# Management_of_Charging_Discharging_Tri-a.net
KiCad netlist of a schematic drawn in Altium Designer
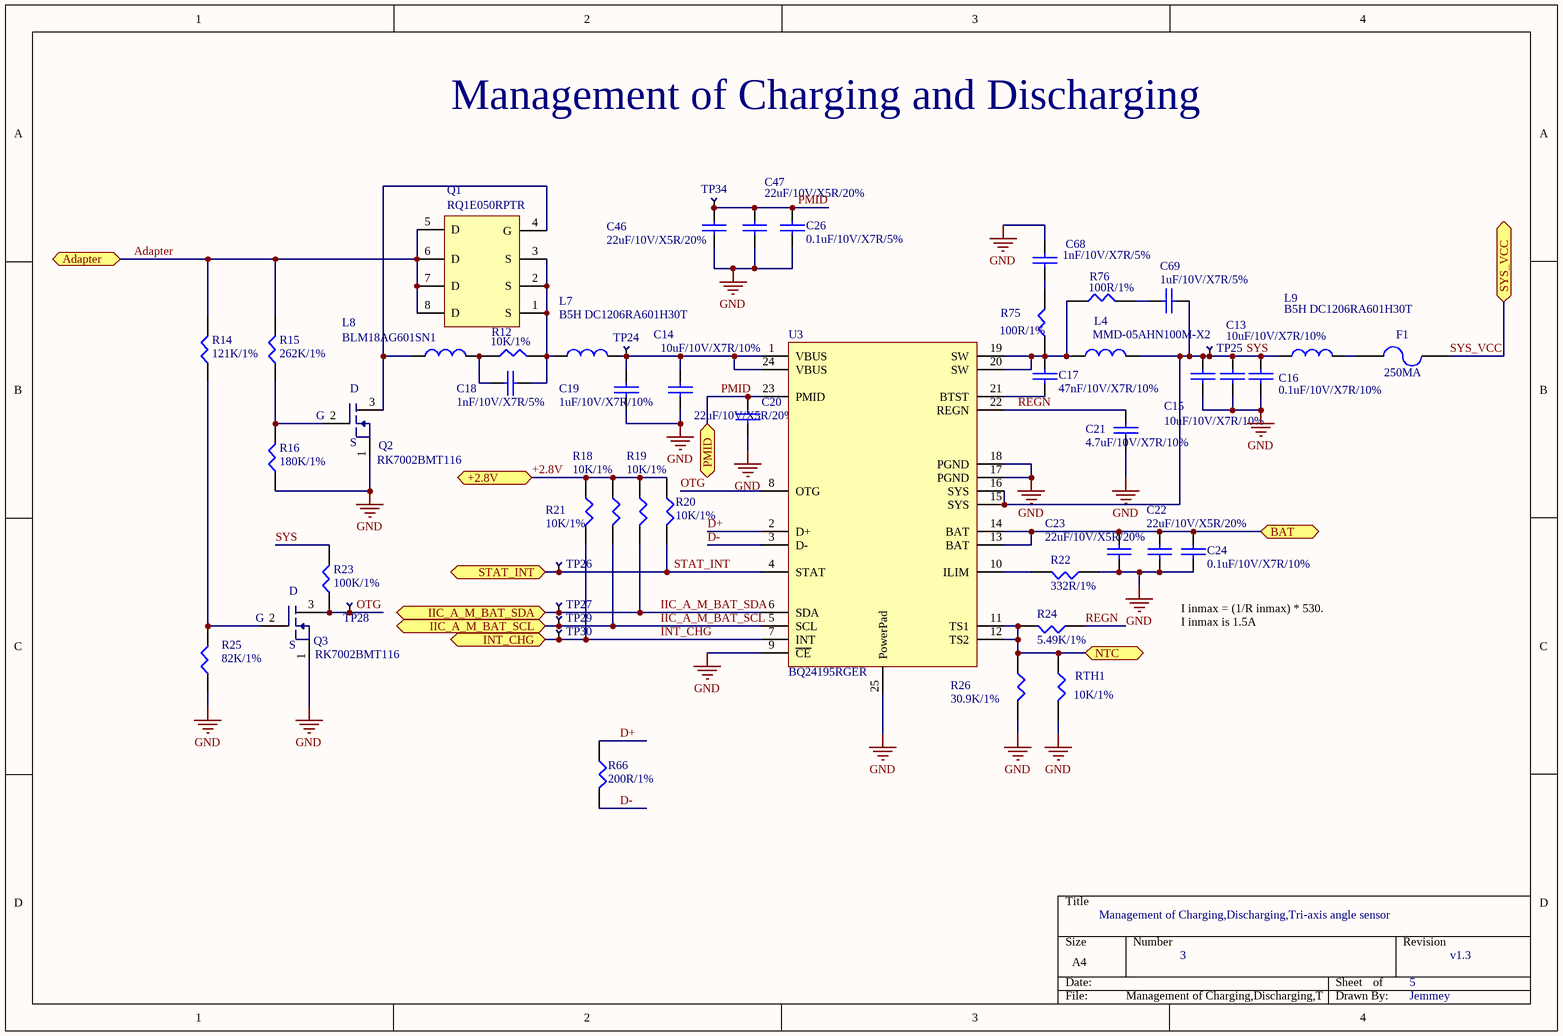
[diagram p0: Management of Charging,Discharging,Tri-axis angle sensor.SchDoc]

(export (version "E")
  (design (tool "Eeschema 10.0.6"))
  (components
    (comp (ref "C13")
      (value "10uF/10V/X7R/10%")
      (footprint "0603C")
      (description "厂家：Murata，型号：GRM188R61A106KE69D")
      (libsource (lib "*") (part "CAP"))
    )
    (comp (ref "C14")
      (value "10uF/10V/X7R/10%")
      (footprint "0603C")
      (description "厂家：Murata，型号：GRM188R61A106KE69D")
      (libsource (lib "*") (part "CAP"))
    )
    (comp (ref "C15")
      (value "10uF/10V/X7R/10%")
      (footprint "0603C")
      (description "厂家：Murata，型号：GRM188R61A106KE69D")
      (libsource (lib "*") (part "CAP"))
    )
    (comp (ref "C16")
      (value "0.1uF/10V/X7R/10%")
      (footprint "0402C")
      (description "厂家：Murata，型号：GRM155R71A104KA01D")
      (libsource (lib "*") (part "CAP"))
    )
    (comp (ref "C17")
      (value "47nF/10V/X7R/10%")
      (footprint "0402C")
      (description "厂家：Murata，型号：GRM155R71H473KE14D")
      (libsource (lib "*") (part "CAP"))
    )
    (comp (ref "C18")
      (value "1nF/10V/X7R/5%")
      (footprint "0402C")
      (description "厂家：Murata，型号：GRM1555C1H102JA01D")
      (libsource (lib "*") (part "CAP"))
    )
    (comp (ref "C19")
      (value "1uF/10V/X7R/10%")
      (footprint "0402C")
      (description "厂家：Murata，型号：GRM155R61C105KA12D")
      (libsource (lib "*") (part "CAP"))
    )
    (comp (ref "C20")
      (value "22uF/10V/X5R/20%")
      (footprint "0603C")
      (description "厂家：Murata，型号：GRM188R61A226ME15D")
      (libsource (lib "*") (part "CAP"))
    )
    (comp (ref "C21")
      (value "4.7uF/10V/X7R/10%")
      (footprint "0603C")
      (description "厂家：Murata，型号：GRM188R61A475KE15D")
      (libsource (lib "*") (part "CAP"))
    )
    (comp (ref "C22")
      (value "22uF/10V/X5R/20%")
      (footprint "0603C")
      (description "厂家：Murata，型号：GRM188R61A226ME15D")
      (libsource (lib "*") (part "CAP"))
    )
    (comp (ref "C23")
      (value "22uF/10V/X5R/20%")
      (footprint "0603C")
      (description "厂家：Murata，型号：GRM188R61A226ME15D")
      (libsource (lib "*") (part "CAP"))
    )
    (comp (ref "C24")
      (value "0.1uF/10V/X7R/10%")
      (footprint "0402C")
      (description "厂家：Murata，型号：GRM155R71A104KA01D")
      (libsource (lib "*") (part "CAP"))
    )
    (comp (ref "C26")
      (value "0.1uF/10V/X7R/5%")
      (footprint "0402C")
      (description "厂家：Murata，型号：GRM1555C1H102JA01D")
      (libsource (lib "*") (part "CAP"))
    )
    (comp (ref "C46")
      (value "22uF/10V/X5R/20%")
      (footprint "0603C")
      (description "厂家：Murata，型号：GRM188R61A226ME15D")
      (libsource (lib "*") (part "CAP"))
    )
    (comp (ref "C47")
      (value "22uF/10V/X5R/20%")
      (footprint "0603C")
      (description "厂家：Murata，型号：GRM188R61A226ME15D")
      (libsource (lib "*") (part "CAP"))
    )
    (comp (ref "C68")
      (value "1nF/10V/X7R/5%")
      (footprint "0603C")
      (description "厂家：Murata，型号：")
      (libsource (lib "*") (part "CAP"))
    )
    (comp (ref "C69")
      (value "1uF/10V/X7R/5%")
      (footprint "0603C")
      (description "厂家：Murata，型号：GRM1555C1H102JA01D")
      (libsource (lib "*") (part "CAP"))
    )
    (comp (ref "F1")
      (value "250MA")
      (footprint "1206-FUSE")
      (description "厂家：万瑞和，型号：WH1206-050")
      (libsource (lib "*") (part "FUSE2"))
    )
    (comp (ref "L4")
      (value "MMD-05AHN100M-X2")
      (footprint "MMD")
      (description "厂家：Mag，型号：MMD-05AHN100M-X2")
      (libsource (lib "Amber") (part "CHOKE"))
    )
    (comp (ref "L7")
      (value "B5H DC1206RA601H30T")
      (footprint "1206")
      (description "厂家：宇磁，型号：B5H DC1206RA601H30T")
      (libsource (lib "Amber") (part "CHOKE"))
    )
    (comp (ref "L8")
      (value "BLM18AG601SN1")
      (footprint "0603R")
      (description "厂家：MURATA，型号：BLM18AG601SN1")
      (libsource (lib "Amber") (part "CHOKE"))
    )
    (comp (ref "L9")
      (value "B5H DC1206RA601H30T")
      (footprint "1206")
      (description "厂家：宇磁，型号：B5H DC1206RA601H30T")
      (libsource (lib "Amber") (part "CHOKE"))
    )
    (comp (ref "Q1")
      (value "RQ1E050RPTR")
      (footprint "TSMT8")
      (description "厂家：ROHM，型号：   RQ1E050RPTR")
      (libsource (lib "Amber") (part "RQ1E050RP"))
    )
    (comp (ref "Q2")
      (value "RK7002BMT116")
      (footprint "SOT23")
      (description "厂家：Vishay，型号：RK7002BMT116")
      (libsource (lib "Amber") (part "RK7002BMT116"))
    )
    (comp (ref "Q3")
      (value "RK7002BMT116")
      (footprint "SOT23")
      (description "厂家：Vishay，型号：RK7002BMT116")
      (libsource (lib "Amber") (part "RK7002BMT116"))
    )
    (comp (ref "R12")
      (value "10K/1%")
      (footprint "0402R")
      (description "厂家：Yageo，型号：RC0402FR-0710KL")
      (libsource (lib "*") (part "RES1"))
    )
    (comp (ref "R14")
      (value "121K/1%")
      (footprint "0402R")
      (description "厂家：Yageo，型号：RC0402FR-07121KL")
      (libsource (lib "*") (part "RES1"))
    )
    (comp (ref "R15")
      (value "262K/1%")
      (footprint "0402R")
      (description "厂家：Yageo，型号：RC0402FR-07262KL")
      (libsource (lib "*") (part "RES1"))
    )
    (comp (ref "R16")
      (value "180K/1%")
      (footprint "0402R")
      (description "厂家：Yageo，型号：RC0402FR-07180KL")
      (libsource (lib "*") (part "RES1"))
    )
    (comp (ref "R18")
      (value "10K/1%")
      (footprint "0402R")
      (description "厂家：Yageo，型号：RC0402FR-0710KL")
      (libsource (lib "*") (part "RES1"))
    )
    (comp (ref "R19")
      (value "10K/1%")
      (footprint "0402R")
      (description "厂家：Yageo，型号：RC0402FR-0710KL")
      (libsource (lib "*") (part "RES1"))
    )
    (comp (ref "R20")
      (value "10K/1%")
      (footprint "0402R")
      (description "厂家：Yageo，型号：RC0402FR-0710KL")
      (libsource (lib "*") (part "RES1"))
    )
    (comp (ref "R21")
      (value "10K/1%")
      (footprint "0402R")
      (description "厂家：Yageo，型号：RC0402FR-0710KL")
      (libsource (lib "*") (part "RES1"))
    )
    (comp (ref "R22")
      (value "332R/1%")
      (footprint "0402R")
      (description "厂家：Yageo，型号：RC0402FR-07332RL")
      (libsource (lib "*") (part "RES1"))
    )
    (comp (ref "R23")
      (value "100K/1%")
      (footprint "0402R")
      (description "厂家：Yageo，型号：RC0402FR-07100KL")
      (libsource (lib "*") (part "RES1"))
    )
    (comp (ref "R24")
      (value "5.49K/1%")
      (footprint "0402R")
      (description "厂家：Yageo，型号：RC0402FR-075K49L")
      (libsource (lib "*") (part "RES1"))
    )
    (comp (ref "R25")
      (value "82K/1%")
      (footprint "0402R")
      (description "厂家：Yageo，型号：RC0402FR-0782KL")
      (libsource (lib "*") (part "RES1"))
    )
    (comp (ref "R26")
      (value "30.9K/1%")
      (footprint "0402R")
      (description "厂家：Yageo，型号：RC0402FR-0730K9L")
      (libsource (lib "*") (part "RES1"))
    )
    (comp (ref "R66")
      (value "200R/1%")
      (footprint "0402R")
      (description "厂家：Yageo，型号：RC0402FR-07200RL")
      (libsource (lib "*") (part "RES1"))
    )
    (comp (ref "R75")
      (value "100R/1%")
      (footprint "0603R")
      (description "厂家：Yageo，型号：RC0402FR-0710KL")
      (libsource (lib "*") (part "RES1"))
    )
    (comp (ref "R76")
      (value "100R/1%")
      (footprint "0603R")
      (description "厂家：Yageo，型号：RC0402FR-0710KL")
      (libsource (lib "*") (part "RES1"))
    )
    (comp (ref "RTH1")
      (value "10K/1%")
      (footprint "0402R")
      (description "厂家：Yageo，型号：RC0402FR-0710KL")
      (libsource (lib "*") (part "RES1"))
    )
    (comp (ref "TP24")
      (value "TEST")
      (footprint "Test Pad")
      (description "Test Point")
      (libsource (lib "Amber") (part "TEST"))
    )
    (comp (ref "TP25")
      (value "TEST")
      (footprint "Test Pad")
      (description "Test Point")
      (libsource (lib "Amber") (part "TEST"))
    )
    (comp (ref "TP26")
      (value "TEST")
      (footprint "Test Pad")
      (description "Test Point")
      (libsource (lib "Amber") (part "TEST"))
    )
    (comp (ref "TP27")
      (value "TEST")
      (footprint "Test Pad")
      (description "Test Point")
      (libsource (lib "Amber") (part "TEST"))
    )
    (comp (ref "TP28")
      (value "TEST")
      (footprint "Test Pad")
      (description "Test Point")
      (libsource (lib "Amber") (part "TEST"))
    )
    (comp (ref "TP29")
      (value "TEST")
      (footprint "Test Pad")
      (description "Test Point")
      (libsource (lib "Amber") (part "TEST"))
    )
    (comp (ref "TP30")
      (value "TEST")
      (footprint "Test Pad")
      (description "Test Point")
      (libsource (lib "Amber") (part "TEST"))
    )
    (comp (ref "TP34")
      (value "TEST")
      (footprint "Test Pad")
      (description "Test Point")
      (libsource (lib "Amber") (part "TEST"))
    )
    (comp (ref "U3")
      (value "BQ24195RGER")
      (footprint "RGE")
      (description "厂家：TI，型号：BQ24195RGER")
      (libsource (lib "Amber") (part "BQ24195L"))
    )
  )
  (nets
    (net (code "1") (name "/+2.8V") (class "Default")
      (node (ref "R18") (pin "1") (pinfunction "1_1") (pintype "passive"))
      (node (ref "R19") (pin "1") (pinfunction "1_1") (pintype "passive"))
      (node (ref "R20") (pin "1") (pinfunction "1_1") (pintype "passive"))
      (node (ref "R21") (pin "1") (pinfunction "1_1") (pintype "passive"))
    )
    (net (code "2") (name "/Adapter") (class "Default")
      (node (ref "Q1") (pin "5") (pinfunction "D_5") (pintype "passive"))
      (node (ref "Q1") (pin "6") (pinfunction "D_6") (pintype "passive"))
      (node (ref "Q1") (pin "7") (pinfunction "D_7") (pintype "passive"))
      (node (ref "Q1") (pin "8") (pinfunction "D_8") (pintype "passive"))
      (node (ref "R14") (pin "2") (pinfunction "2_2") (pintype "passive"))
      (node (ref "R15") (pin "2") (pinfunction "2_2") (pintype "passive"))
    )
    (net (code "3") (name "/BAT") (class "Default")
      (node (ref "C22") (pin "1") (pinfunction "1_1") (pintype "passive"))
      (node (ref "C23") (pin "1") (pinfunction "1_1") (pintype "passive"))
      (node (ref "C24") (pin "1") (pinfunction "1_1") (pintype "passive"))
      (node (ref "U3") (pin "13") (pinfunction "BAT_13") (pintype "passive"))
      (node (ref "U3") (pin "14") (pinfunction "BAT_14") (pintype "passive"))
    )
    (net (code "4") (name "/D+") (class "Default")
      (node (ref "R66") (pin "1") (pinfunction "1_1") (pintype "passive"))
      (node (ref "U3") (pin "2") (pinfunction "D+_2") (pintype "passive"))
    )
    (net (code "5") (name "/D-") (class "Default")
      (node (ref "R66") (pin "2") (pinfunction "2_2") (pintype "passive"))
      (node (ref "U3") (pin "3") (pinfunction "D-_3") (pintype "passive"))
    )
    (net (code "6") (name "/IIC_A_M_BAT_SCL") (class "Default")
      (node (ref "R18") (pin "2") (pinfunction "2_2") (pintype "passive"))
      (node (ref "TP29") (pin "1") (pinfunction "1_1") (pintype "passive"))
      (node (ref "U3") (pin "5") (pinfunction "SCL_5") (pintype "passive"))
    )
    (net (code "7") (name "/IIC_A_M_BAT_SDA") (class "Default")
      (node (ref "R19") (pin "2") (pinfunction "2_2") (pintype "passive"))
      (node (ref "TP27") (pin "1") (pinfunction "1_1") (pintype "passive"))
      (node (ref "U3") (pin "6") (pinfunction "SDA_6") (pintype "passive"))
    )
    (net (code "8") (name "/INT_CHG") (class "Default")
      (node (ref "R21") (pin "2") (pinfunction "2_2") (pintype "passive"))
      (node (ref "TP30") (pin "1") (pinfunction "1_1") (pintype "passive"))
      (node (ref "U3") (pin "7") (pinfunction "INT_7") (pintype "passive"))
    )
    (net (code "9") (name "/NTC") (class "Default")
      (node (ref "R24") (pin "2") (pinfunction "2_2") (pintype "passive"))
      (node (ref "R26") (pin "1") (pinfunction "1_1") (pintype "passive"))
      (node (ref "RTH1") (pin "1") (pinfunction "1_1") (pintype "passive"))
      (node (ref "U3") (pin "11") (pinfunction "TS1_11") (pintype "passive"))
      (node (ref "U3") (pin "12") (pinfunction "TS2_12") (pintype "passive"))
    )
    (net (code "10") (name "/OTG") (class "Default")
      (node (ref "Q3") (pin "3") (pinfunction "D_3") (pintype "passive"))
      (node (ref "R23") (pin "1") (pinfunction "1_1") (pintype "passive"))
      (node (ref "TP28") (pin "1") (pinfunction "1_1") (pintype "passive"))
      (node (ref "U3") (pin "8") (pinfunction "OTG_8") (pintype "passive"))
    )
    (net (code "11") (name "/PMID") (class "Default")
      (node (ref "C20") (pin "1") (pinfunction "1_1") (pintype "passive"))
      (node (ref "C26") (pin "2") (pinfunction "2_2") (pintype "passive"))
      (node (ref "C46") (pin "1") (pinfunction "1_1") (pintype "passive"))
      (node (ref "C47") (pin "1") (pinfunction "1_1") (pintype "passive"))
      (node (ref "TP34") (pin "1") (pinfunction "1_1") (pintype "passive"))
      (node (ref "U3") (pin "23") (pinfunction "PMID_23") (pintype "passive"))
    )
    (net (code "12") (name "/REGN") (class "Default")
      (node (ref "C21") (pin "1") (pinfunction "1_1") (pintype "passive"))
      (node (ref "R24") (pin "1") (pinfunction "1_1") (pintype "passive"))
      (node (ref "U3") (pin "22") (pinfunction "REGN_22") (pintype "passive"))
    )
    (net (code "13") (name "/STAT_INT") (class "Default")
      (node (ref "R20") (pin "2") (pinfunction "2_2") (pintype "passive"))
      (node (ref "TP26") (pin "1") (pinfunction "1_1") (pintype "passive"))
      (node (ref "U3") (pin "4") (pinfunction "STAT_4") (pintype "passive"))
    )
    (net (code "14") (name "/SYS") (class "Default")
      (node (ref "C13") (pin "1") (pinfunction "1_1") (pintype "passive"))
      (node (ref "C15") (pin "1") (pinfunction "1_1") (pintype "passive"))
      (node (ref "C16") (pin "1") (pinfunction "1_1") (pintype "passive"))
      (node (ref "C69") (pin "1") (pinfunction "1_1") (pintype "passive"))
      (node (ref "L4") (pin "2") (pinfunction "2_2") (pintype "passive"))
      (node (ref "L9") (pin "1") (pinfunction "1_1") (pintype "passive"))
      (node (ref "R23") (pin "2") (pinfunction "2_2") (pintype "passive"))
      (node (ref "TP25") (pin "1") (pinfunction "1_1") (pintype "passive"))
      (node (ref "U3") (pin "15") (pinfunction "SYS_15") (pintype "passive"))
      (node (ref "U3") (pin "16") (pinfunction "SYS_16") (pintype "passive"))
    )
    (net (code "15") (name "/SYS_VCC") (class "Default")
      (node (ref "F1") (pin "1") (pinfunction "1_1") (pintype "passive"))
    )
    (net (code "16") (name "GND") (class "Default")
      (node (ref "C13") (pin "2") (pinfunction "2_2") (pintype "passive"))
      (node (ref "C14") (pin "2") (pinfunction "2_2") (pintype "passive"))
      (node (ref "C15") (pin "2") (pinfunction "2_2") (pintype "passive"))
      (node (ref "C16") (pin "2") (pinfunction "2_2") (pintype "passive"))
      (node (ref "C19") (pin "2") (pinfunction "2_2") (pintype "passive"))
      (node (ref "C20") (pin "2") (pinfunction "2_2") (pintype "passive"))
      (node (ref "C21") (pin "2") (pinfunction "2_2") (pintype "passive"))
      (node (ref "C22") (pin "2") (pinfunction "2_2") (pintype "passive"))
      (node (ref "C23") (pin "2") (pinfunction "2_2") (pintype "passive"))
      (node (ref "C24") (pin "2") (pinfunction "2_2") (pintype "passive"))
      (node (ref "C26") (pin "1") (pinfunction "1_1") (pintype "passive"))
      (node (ref "C46") (pin "2") (pinfunction "2_2") (pintype "passive"))
      (node (ref "C47") (pin "2") (pinfunction "2_2") (pintype "passive"))
      (node (ref "C68") (pin "2") (pinfunction "2_2") (pintype "passive"))
      (node (ref "Q2") (pin "1") (pinfunction "S_1") (pintype "passive"))
      (node (ref "Q3") (pin "1") (pinfunction "S_1") (pintype "passive"))
      (node (ref "R16") (pin "1") (pinfunction "1_1") (pintype "passive"))
      (node (ref "R22") (pin "1") (pinfunction "1_1") (pintype "passive"))
      (node (ref "R25") (pin "1") (pinfunction "1_1") (pintype "passive"))
      (node (ref "R26") (pin "2") (pinfunction "2_2") (pintype "passive"))
      (node (ref "RTH1") (pin "2") (pinfunction "2_2") (pintype "passive"))
      (node (ref "U3") (pin "17") (pinfunction "PGND_17") (pintype "passive"))
      (node (ref "U3") (pin "18") (pinfunction "PGND_18") (pintype "passive"))
      (node (ref "U3") (pin "25") (pinfunction "PowerPad_25") (pintype "passive"))
      (node (ref "U3") (pin "9") (pinfunction "~{CE}_9") (pintype "passive"))
    )
    (net (code "17") (name "Net-(C14-Pad1)") (class "Default")
      (node (ref "C14") (pin "1") (pinfunction "1_1") (pintype "passive"))
      (node (ref "C19") (pin "1") (pinfunction "1_1") (pintype "passive"))
      (node (ref "L7") (pin "2") (pinfunction "2_2") (pintype "passive"))
      (node (ref "TP24") (pin "1") (pinfunction "1_1") (pintype "passive"))
      (node (ref "U3") (pin "1") (pinfunction "VBUS_1") (pintype "passive"))
      (node (ref "U3") (pin "24") (pinfunction "VBUS_24") (pintype "passive"))
    )
    (net (code "18") (name "Net-(C17-Pad1)") (class "Default")
      (node (ref "C17") (pin "1") (pinfunction "1_1") (pintype "passive"))
      (node (ref "L4") (pin "1") (pinfunction "1_1") (pintype "passive"))
      (node (ref "R75") (pin "1") (pinfunction "1_1") (pintype "passive"))
      (node (ref "R76") (pin "1") (pinfunction "1_1") (pintype "passive"))
      (node (ref "U3") (pin "19") (pinfunction "SW_19") (pintype "passive"))
      (node (ref "U3") (pin "20") (pinfunction "SW_20") (pintype "passive"))
    )
    (net (code "19") (name "Net-(C18-Pad1)") (class "Default")
      (node (ref "C18") (pin "1") (pinfunction "1_1") (pintype "passive"))
      (node (ref "L8") (pin "2") (pinfunction "2_2") (pintype "passive"))
      (node (ref "R12") (pin "1") (pinfunction "1_1") (pintype "passive"))
    )
    (net (code "20") (name "Net-(C18-Pad2)") (class "Default")
      (node (ref "C18") (pin "2") (pinfunction "2_2") (pintype "passive"))
      (node (ref "L7") (pin "1") (pinfunction "1_1") (pintype "passive"))
      (node (ref "Q1") (pin "1") (pinfunction "S_1") (pintype "passive"))
      (node (ref "Q1") (pin "2") (pinfunction "S_2") (pintype "passive"))
      (node (ref "Q1") (pin "3") (pinfunction "S_3") (pintype "passive"))
      (node (ref "R12") (pin "2") (pinfunction "2_2") (pintype "passive"))
    )
    (net (code "21") (name "Net-(C68-Pad1)") (class "Default")
      (node (ref "C68") (pin "1") (pinfunction "1_1") (pintype "passive"))
      (node (ref "R75") (pin "2") (pinfunction "2_2") (pintype "passive"))
    )
    (net (code "22") (name "Net-(C69-Pad2)") (class "Default")
      (node (ref "C69") (pin "2") (pinfunction "2_2") (pintype "passive"))
      (node (ref "R76") (pin "2") (pinfunction "2_2") (pintype "passive"))
    )
    (net (code "23") (name "Net-(F1-Pad2)") (class "Default")
      (node (ref "F1") (pin "2") (pinfunction "2_2") (pintype "passive"))
      (node (ref "L9") (pin "2") (pinfunction "2_2") (pintype "passive"))
    )
    (net (code "24") (name "Net-(Q1-G)") (class "Default")
      (node (ref "L8") (pin "1") (pinfunction "1_1") (pintype "passive"))
      (node (ref "Q1") (pin "4") (pinfunction "G_4") (pintype "passive"))
      (node (ref "Q2") (pin "3") (pinfunction "D_3") (pintype "passive"))
    )
    (net (code "25") (name "Net-(Q2-G)") (class "Default")
      (node (ref "Q2") (pin "2") (pinfunction "G_2") (pintype "passive"))
      (node (ref "R15") (pin "1") (pinfunction "1_1") (pintype "passive"))
      (node (ref "R16") (pin "2") (pinfunction "2_2") (pintype "passive"))
    )
    (net (code "26") (name "Net-(Q3-G)") (class "Default")
      (node (ref "Q3") (pin "2") (pinfunction "G_2") (pintype "passive"))
      (node (ref "R14") (pin "1") (pinfunction "1_1") (pintype "passive"))
      (node (ref "R25") (pin "2") (pinfunction "2_2") (pintype "passive"))
    )
    (net (code "27") (name "Net-(U3-BTST)") (class "Default")
      (node (ref "C17") (pin "2") (pinfunction "2_2") (pintype "passive"))
      (node (ref "U3") (pin "21") (pinfunction "BTST_21") (pintype "passive"))
    )
    (net (code "28") (name "Net-(U3-ILIM)") (class "Default")
      (node (ref "R22") (pin "2") (pinfunction "2_2") (pintype "passive"))
      (node (ref "U3") (pin "10") (pinfunction "ILIM_10") (pintype "passive"))
    )
  )
)
